# Power_Amplifier.net
KiCad netlist of a schematic drawn in Altium Designer
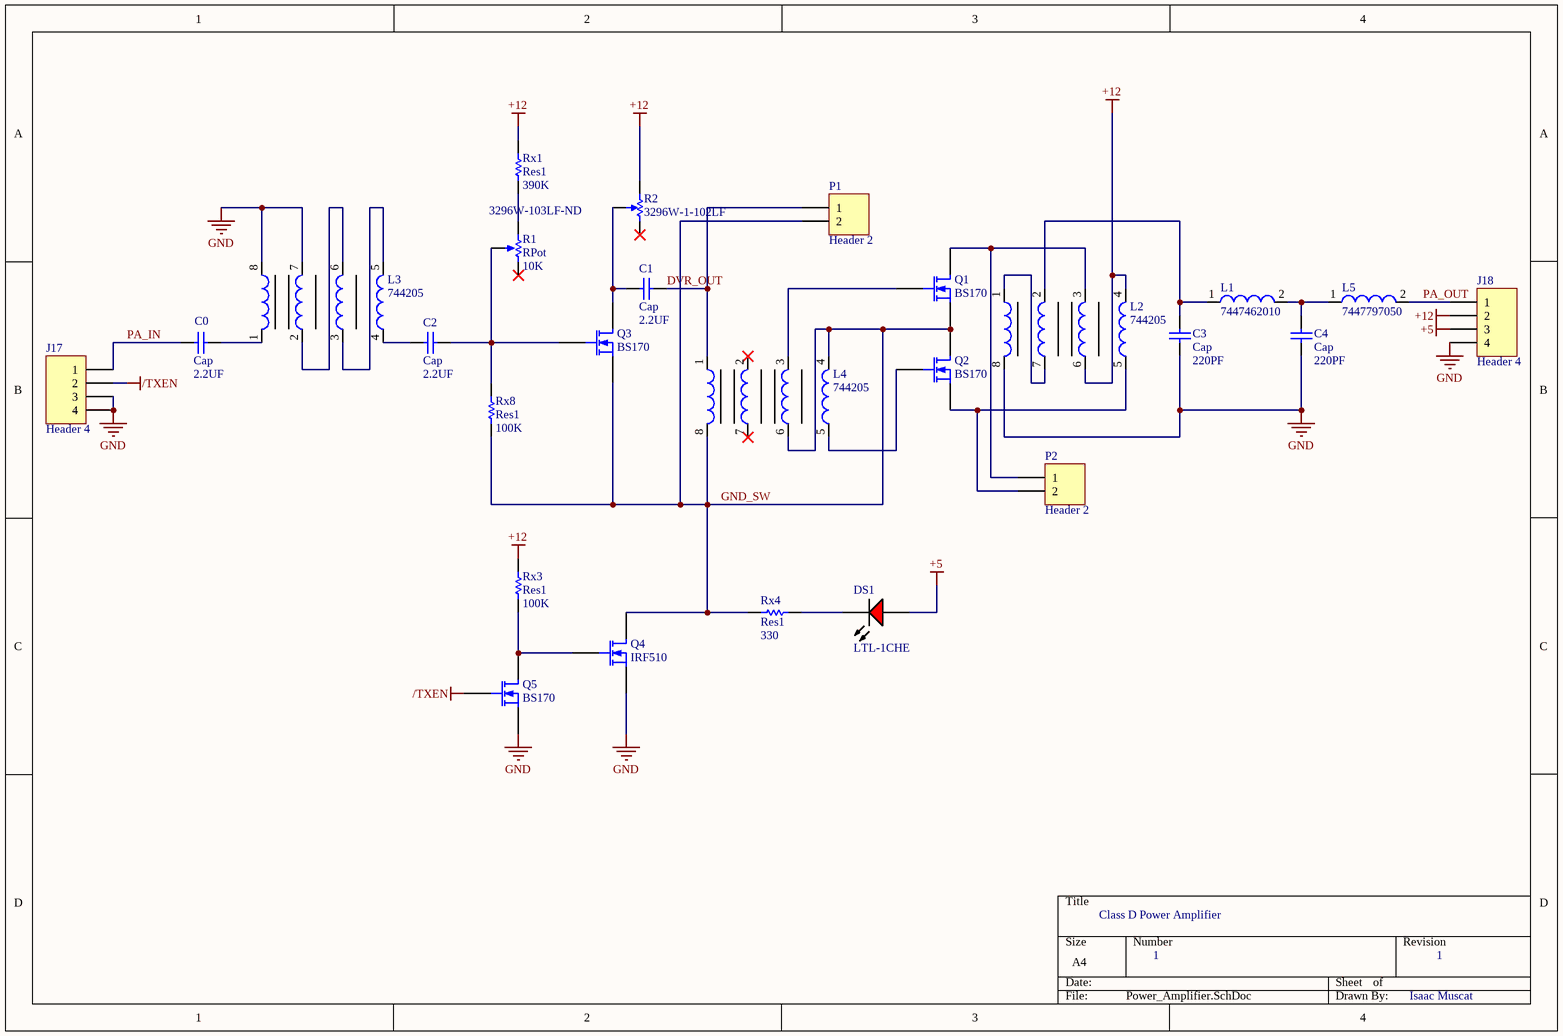
[diagram p0: Power_Amplifier.SchDoc]

(export (version "E")
  (design (tool "Eeschema 10.0.6"))
  (components
    (comp (ref "C0")
      (value "Cap")
      (footprint "RADIAL-0.1")
      (description "Capacitor")
      (fields
        (field (name "ALTIUM_VALUE") "2.2UF")
        (field (name "MANUFACTURER PART NUMBER") "C330C225M5U5TA7303")
        (field (name "PUBLISHER") "Altium Limited")
      )
      (libsource (lib "ECE295-Capacitors-TH") (part "CAP CER 2.2UF 50V Z5U RADIAL"))
    )
    (comp (ref "C1")
      (value "Cap")
      (footprint "RADIAL-0.1")
      (description "Capacitor")
      (fields
        (field (name "ALTIUM_VALUE") "2.2UF")
        (field (name "MANUFACTURER PART NUMBER") "C330C225M5U5TA7303")
        (field (name "PUBLISHER") "Altium Limited")
      )
      (libsource (lib "ECE295-Capacitors-TH") (part "CAP CER 2.2UF 50V Z5U RADIAL"))
    )
    (comp (ref "C2")
      (value "Cap")
      (footprint "RADIAL-0.1")
      (description "Capacitor")
      (fields
        (field (name "ALTIUM_VALUE") "2.2UF")
        (field (name "MANUFACTURER PART NUMBER") "C330C225M5U5TA7303")
        (field (name "PUBLISHER") "Altium Limited")
      )
      (libsource (lib "ECE295-Capacitors-TH") (part "CAP CER 2.2UF 50V Z5U RADIAL"))
    )
    (comp (ref "C3")
      (value "Cap")
      (footprint "RADIAL-0.1")
      (description "Capacitor")
      (fields
        (field (name "ALTIUM_VALUE") "220PF")
        (field (name "MANUFACTURER PART NUMBER") "K221K15X7RF5TH5")
        (field (name "PUBLISHER") "Altium Limited")
      )
      (libsource (lib "ECE295-Capacitors-TH") (part "CAP CER 220PF 50V X7R RADIAL"))
    )
    (comp (ref "C4")
      (value "Cap")
      (footprint "RADIAL-0.1")
      (description "Capacitor")
      (fields
        (field (name "ALTIUM_VALUE") "220PF")
        (field (name "MANUFACTURER PART NUMBER") "K221K15X7RF5TH5")
        (field (name "PUBLISHER") "Altium Limited")
      )
      (libsource (lib "ECE295-Capacitors-TH") (part "CAP CER 220PF 50V X7R RADIAL"))
    )
    (comp (ref "DS1")
      (value "LTL-1CHE")
      (footprint "INDPR60-254-520X380X650")
      (description "Radial LED, 12.6 mcd, 20 mA, 2 V, -55 to 100 degC, 2-Pin THD, RoHS, Bulk")
      (fields (field (name "TOLERANCE") "20%"))
      (libsource (lib "Altium Content Vault") (part "LED-RED-AK-2"))
    )
    (comp (ref "J17")
      (value "Header 4")
      (footprint "HDR1X4")
      (description "Header, 4-Pin")
      (fields (field (name "PUBLISHER") "Altium Limited"))
      (libsource (lib "") (part "Header 4_1"))
    )
    (comp (ref "J18")
      (value "Header 4")
      (footprint "HDR1X4")
      (description "Header, 4-Pin")
      (fields (field (name "PUBLISHER") "Altium Limited"))
      (libsource (lib "Miscellaneous Connectors") (part "Header 4"))
    )
    (comp (ref "L1")
      (value "7447462010")
      (footprint "WE-TI-XS")
      (description "Radial Leaded Wire Wound Inductor WE-TI, L = 1.00 µH")
      (libsource (lib "Altium Content Vault") (part "PAS-IND-INDUCTOR-2"))
    )
    (comp (ref "L2")
      (value "744205")
      (footprint "WE-SL")
      (description "SMD Common Mode Line Filter WE-SL, L = 100 µH")
      (libsource (lib "Altium Content Vault") (part "PAS-IND-INDUCTOR-8"))
    )
    (comp (ref "L3")
      (value "744205")
      (footprint "WE-SL")
      (description "SMD Common Mode Line Filter WE-SL, L = 100 µH")
      (libsource (lib "") (part "PAS-IND-INDUCTOR-8_1"))
    )
    (comp (ref "L4")
      (value "744205")
      (footprint "WE-SL")
      (description "SMD Common Mode Line Filter WE-SL, L = 100 µH")
      (libsource (lib "Altium Content Vault") (part "PAS-IND-INDUCTOR-8"))
    )
    (comp (ref "L5")
      (value "7447797050")
      (footprint "WE-PDF-1045")
      (description "SMD Power Inductor WE-PDF, L = 0.50 µH")
      (libsource (lib "Altium Content Vault") (part "PAS-IND-INDUCTOR-2"))
    )
    (comp (ref "P1")
      (value "Header 2")
      (footprint "HDR1X2")
      (description "Header, 2-Pin")
      (fields (field (name "PUBLISHER") "Altium Limited"))
      (libsource (lib "Miscellaneous Connectors") (part "Header 2"))
    )
    (comp (ref "P2")
      (value "Header 2")
      (footprint "HDR1X2")
      (description "Header, 2-Pin")
      (fields (field (name "PUBLISHER") "Altium Limited"))
      (libsource (lib "Miscellaneous Connectors") (part "Header 2"))
    )
    (comp (ref "Q1")
      (value "BS170")
      (footprint "TO-92")
      (description "N-Channel MOSFET")
      (fields (field (name "PUBLISHER") "Altium Limited"))
      (libsource (lib "Miscellaneous Devices") (part "MOSFET-N"))
    )
    (comp (ref "Q2")
      (value "BS170")
      (footprint "TO-92")
      (description "N-Channel MOSFET")
      (fields (field (name "PUBLISHER") "Altium Limited"))
      (libsource (lib "Miscellaneous Devices") (part "MOSFET-N"))
    )
    (comp (ref "Q3")
      (value "BS170")
      (footprint "TO-92")
      (description "N-Channel MOSFET")
      (fields (field (name "PUBLISHER") "Altium Limited"))
      (libsource (lib "Miscellaneous Devices") (part "MOSFET-N"))
    )
    (comp (ref "Q4")
      (value "IRF510")
      (footprint "TO-220AB")
      (description "N-Channel MOSFET")
      (fields (field (name "PUBLISHER") "Altium Limited"))
      (libsource (lib "Miscellaneous Devices") (part "MOSFET-N"))
    )
    (comp (ref "Q5")
      (value "BS170")
      (footprint "TO-92")
      (description "N-Channel MOSFET")
      (fields (field (name "PUBLISHER") "Altium Limited"))
      (libsource (lib "Miscellaneous Devices") (part "MOSFET-N"))
    )
    (comp (ref "R1")
      (value "RPot")
      (footprint "VR5")
      (description "Potentiometer")
      (fields
        (field (name "ALTIUM_VALUE") "10K")
        (field (name "SUPPLIER PART NUMBER 1") "3296W-103LF-ND")
        (field (name "PUBLISHER") "Altium Limited")
      )
      (libsource (lib "Miscellaneous Devices") (part "RPot"))
    )
    (comp (ref "R2")
      (value "3296W-1-102LF")
      (footprint "BOUR-3296W-1-3")
      (description "Square Trimpot(R) Trimming Potentiometer, 1000 Ohm, -55 to 125 degC, 3-Pin THD, RoHS, Tube")
      (fields (field (name "TOLERANCE") "1%"))
      (libsource (lib "Altium Content Vault") (part "RES-ADJ-3"))
    )
    (comp (ref "Rx1")
      (value "Res1")
      (footprint "AXIAL-0.1-RES")
      (description "Resistor")
      (fields
        (field (name "ALTIUM_VALUE") "390K")
        (field (name "MANUFACTURER PART NUMBER") "CFR-25JB-52-390K")
        (field (name "TOLERANCE") "0.05")
        (field (name "PUBLISHER") "Altium Limited")
      )
      (libsource (lib "ECE295-Resistors-TH") (part "RES 390K OHM 5% 1/4W AXIAL"))
    )
    (comp (ref "Rx3")
      (value "Res1")
      (footprint "AXIAL-0.1-RES")
      (description "Resistor")
      (fields
        (field (name "ALTIUM_VALUE") "100K")
        (field (name "MANUFACTURER PART NUMBER") "CFR-25JB-52-10K")
        (field (name "TOLERANCE") "0.05")
        (field (name "PUBLISHER") "Altium Limited")
      )
      (libsource (lib "ECE295-Resistors-TH") (part "RES 10K OHM 5% 1/4W AXIAL"))
    )
    (comp (ref "Rx4")
      (value "Res1")
      (footprint "AXIAL-0.1-RES")
      (description "Resistor")
      (fields
        (field (name "ALTIUM_VALUE") "330")
        (field (name "MANUFACTURER PART NUMBER") "CFR-25JB-52-330R")
        (field (name "TOLERANCE") "0.05")
        (field (name "PUBLISHER") "Altium Limited")
      )
      (libsource (lib "ECE295-Resistors-TH") (part "RES 330 OHM 5% 1/4W AXIAL"))
    )
    (comp (ref "Rx8")
      (value "Res1")
      (footprint "AXIAL-0.1-RES")
      (description "Resistor")
      (fields
        (field (name "ALTIUM_VALUE") "100K")
        (field (name "MANUFACTURER PART NUMBER") "CFR-25JB-52-10K")
        (field (name "TOLERANCE") "0.05")
        (field (name "PUBLISHER") "Altium Limited")
      )
      (libsource (lib "ECE295-Resistors-TH") (part "RES 10K OHM 5% 1/4W AXIAL"))
    )
  )
  (nets
    (net (code "1") (name "+5") (class "Default")
      (node (ref "DS1") (pin "1") (pinfunction "A_1") (pintype "passive"))
      (node (ref "J18") (pin "3") (pinfunction "3_3") (pintype "passive"))
    )
    (net (code "2") (name "+12") (class "Default")
      (node (ref "J18") (pin "2") (pinfunction "2_2") (pintype "passive"))
      (node (ref "L2") (pin "4") (pinfunction "4_4") (pintype "passive"))
      (node (ref "L2") (pin "6") (pinfunction "6_6") (pintype "passive"))
      (node (ref "R2") (pin "1") (pinfunction "A_1") (pintype "passive"))
      (node (ref "Rx1") (pin "2") (pinfunction "2_2") (pintype "passive"))
      (node (ref "Rx3") (pin "1") (pinfunction "1_1") (pintype "passive"))
    )
    (net (code "3") (name "/DVR_OUT") (class "Default")
      (node (ref "C1") (pin "2") (pinfunction "2_2") (pintype "passive"))
      (node (ref "L4") (pin "1") (pinfunction "1_1") (pintype "passive"))
      (node (ref "P1") (pin "1") (pinfunction "1_1") (pintype "passive"))
    )
    (net (code "4") (name "/GND_SW") (class "Default")
      (node (ref "L4") (pin "4") (pinfunction "4_4") (pintype "passive"))
      (node (ref "L4") (pin "6") (pinfunction "6_6") (pintype "passive"))
      (node (ref "L4") (pin "8") (pinfunction "8_8") (pintype "passive"))
      (node (ref "P1") (pin "2") (pinfunction "2_2") (pintype "passive"))
      (node (ref "Q1") (pin "3") (pinfunction "S_3") (pintype "passive"))
      (node (ref "Q2") (pin "1") (pinfunction "D_1") (pintype "passive"))
      (node (ref "Q3") (pin "3") (pinfunction "S_3") (pintype "passive"))
      (node (ref "Q4") (pin "1") (pinfunction "D_1") (pintype "passive"))
      (node (ref "Rx4") (pin "1") (pinfunction "1_1") (pintype "passive"))
      (node (ref "Rx8") (pin "1") (pinfunction "1_1") (pintype "passive"))
    )
    (net (code "5") (name "/PA_IN") (class "Default")
      (node (ref "C0") (pin "1") (pinfunction "1_1") (pintype "passive"))
      (node (ref "J17") (pin "1") (pinfunction "1_1") (pintype "passive"))
    )
    (net (code "6") (name "/PA_OUT") (class "Default")
      (node (ref "J18") (pin "1") (pinfunction "1_1") (pintype "passive"))
      (node (ref "L5") (pin "2") (pinfunction "2_2") (pintype "passive"))
    )
    (net (code "7") (name "GND") (class "Default")
      (node (ref "C3") (pin "1") (pinfunction "1_1") (pintype "passive"))
      (node (ref "C4") (pin "1") (pinfunction "1_1") (pintype "passive"))
      (node (ref "J17") (pin "3") (pinfunction "3_3") (pintype "passive"))
      (node (ref "J17") (pin "4") (pinfunction "4_4") (pintype "passive"))
      (node (ref "J18") (pin "4") (pinfunction "4_4") (pintype "passive"))
      (node (ref "L2") (pin "8") (pinfunction "8_8") (pintype "passive"))
      (node (ref "L3") (pin "7") (pinfunction "7_7") (pintype "passive"))
      (node (ref "L3") (pin "8") (pinfunction "8_8") (pintype "passive"))
      (node (ref "Q4") (pin "3") (pinfunction "S_3") (pintype "passive"))
      (node (ref "Q5") (pin "3") (pinfunction "S_3") (pintype "passive"))
    )
    (net (code "8") (name "Net-(C0-Pad2)") (class "Default")
      (node (ref "C0") (pin "2") (pinfunction "2_2") (pintype "passive"))
      (node (ref "L3") (pin "1") (pinfunction "1_1") (pintype "passive"))
    )
    (net (code "9") (name "Net-(C2-Pad1)") (class "Default")
      (node (ref "C2") (pin "1") (pinfunction "1_1") (pintype "passive"))
      (node (ref "L3") (pin "4") (pinfunction "4_4") (pintype "passive"))
    )
    (net (code "10") (name "Net-(C3-Pad2)") (class "Default")
      (node (ref "C3") (pin "2") (pinfunction "2_2") (pintype "passive"))
      (node (ref "L1") (pin "1") (pinfunction "1_1") (pintype "passive"))
      (node (ref "L2") (pin "2") (pinfunction "2_2") (pintype "passive"))
    )
    (net (code "11") (name "Net-(C4-Pad2)") (class "Default")
      (node (ref "C4") (pin "2") (pinfunction "2_2") (pintype "passive"))
      (node (ref "L1") (pin "2") (pinfunction "2_2") (pintype "passive"))
      (node (ref "L5") (pin "1") (pinfunction "1_1") (pintype "passive"))
    )
    (net (code "12") (name "Net-(DS1-K)") (class "Default")
      (node (ref "DS1") (pin "2") (pinfunction "K_2") (pintype "passive"))
      (node (ref "Rx4") (pin "2") (pinfunction "2_2") (pintype "passive"))
    )
    (net (code "13") (name "Net-(L2-Pad1)") (class "Default")
      (node (ref "L2") (pin "1") (pinfunction "1_1") (pintype "passive"))
      (node (ref "L2") (pin "7") (pinfunction "7_7") (pintype "passive"))
    )
    (net (code "14") (name "Net-(L3-Pad2)") (class "Default")
      (node (ref "L3") (pin "2") (pinfunction "2_2") (pintype "passive"))
      (node (ref "L3") (pin "6") (pinfunction "6_6") (pintype "passive"))
    )
    (net (code "15") (name "Net-(L3-Pad3)") (class "Default")
      (node (ref "L3") (pin "3") (pinfunction "3_3") (pintype "passive"))
      (node (ref "L3") (pin "5") (pinfunction "5_5") (pintype "passive"))
    )
    (net (code "16") (name "Net-(Q1-D)") (class "Default")
      (node (ref "L2") (pin "3") (pinfunction "3_3") (pintype "passive"))
      (node (ref "P2") (pin "1") (pinfunction "1_1") (pintype "passive"))
      (node (ref "Q1") (pin "1") (pinfunction "D_1") (pintype "passive"))
    )
    (net (code "17") (name "Net-(Q1-G)") (class "Default")
      (node (ref "L4") (pin "3") (pinfunction "3_3") (pintype "passive"))
      (node (ref "Q1") (pin "2") (pinfunction "G_2") (pintype "passive"))
    )
    (net (code "18") (name "Net-(Q2-G)") (class "Default")
      (node (ref "L4") (pin "5") (pinfunction "5_5") (pintype "passive"))
      (node (ref "Q2") (pin "2") (pinfunction "G_2") (pintype "passive"))
    )
    (net (code "19") (name "Net-(Q2-S)") (class "Default")
      (node (ref "L2") (pin "5") (pinfunction "5_5") (pintype "passive"))
      (node (ref "P2") (pin "2") (pinfunction "2_2") (pintype "passive"))
      (node (ref "Q2") (pin "3") (pinfunction "S_3") (pintype "passive"))
    )
    (net (code "20") (name "Net-(Q3-D)") (class "Default")
      (node (ref "C1") (pin "1") (pinfunction "1_1") (pintype "passive"))
      (node (ref "Q3") (pin "1") (pinfunction "D_1") (pintype "passive"))
      (node (ref "R2") (pin "3") (pinfunction "TAP_3") (pintype "passive"))
    )
    (net (code "21") (name "Net-(Q3-G)") (class "Default")
      (node (ref "C2") (pin "2") (pinfunction "2_2") (pintype "passive"))
      (node (ref "Q3") (pin "2") (pinfunction "G_2") (pintype "passive"))
      (node (ref "R1") (pin "3") (pinfunction "TAP_3") (pintype "passive"))
      (node (ref "Rx8") (pin "2") (pinfunction "2_2") (pintype "passive"))
    )
    (net (code "22") (name "Net-(Q4-G)") (class "Default")
      (node (ref "Q4") (pin "2") (pinfunction "G_2") (pintype "passive"))
      (node (ref "Q5") (pin "1") (pinfunction "D_1") (pintype "passive"))
      (node (ref "Rx3") (pin "2") (pinfunction "2_2") (pintype "passive"))
    )
    (net (code "23") (name "Net-(R1-TOP)") (class "Default")
      (node (ref "R1") (pin "1") (pinfunction "TOP_1") (pintype "passive"))
      (node (ref "Rx1") (pin "1") (pinfunction "1_1") (pintype "passive"))
    )
    (net (code "24") (name "unconnected-(L4-Pad2)") (class "Default")
      (node (ref "L4") (pin "2") (pinfunction "2_2") (pintype "passive+no_connect"))
    )
    (net (code "25") (name "unconnected-(L4-Pad7)") (class "Default")
      (node (ref "L4") (pin "7") (pinfunction "7_7") (pintype "passive+no_connect"))
    )
    (net (code "26") (name "unconnected-(R1-BOT-Pad2)") (class "Default")
      (node (ref "R1") (pin "2") (pinfunction "BOT_2") (pintype "passive+no_connect"))
    )
    (net (code "27") (name "unconnected-(R2-B-Pad2)") (class "Default")
      (node (ref "R2") (pin "2") (pinfunction "B_2") (pintype "passive+no_connect"))
    )
    (net (code "28") (name "{slash}TXEN") (class "Default")
      (node (ref "J17") (pin "2") (pinfunction "2_2") (pintype "passive"))
      (node (ref "Q5") (pin "2") (pinfunction "G_2") (pintype "passive"))
    )
  )
)
